# bar-graph-driver-16x9-ca-v2.net
KiCad netlist of a schematic drawn in EAGLE
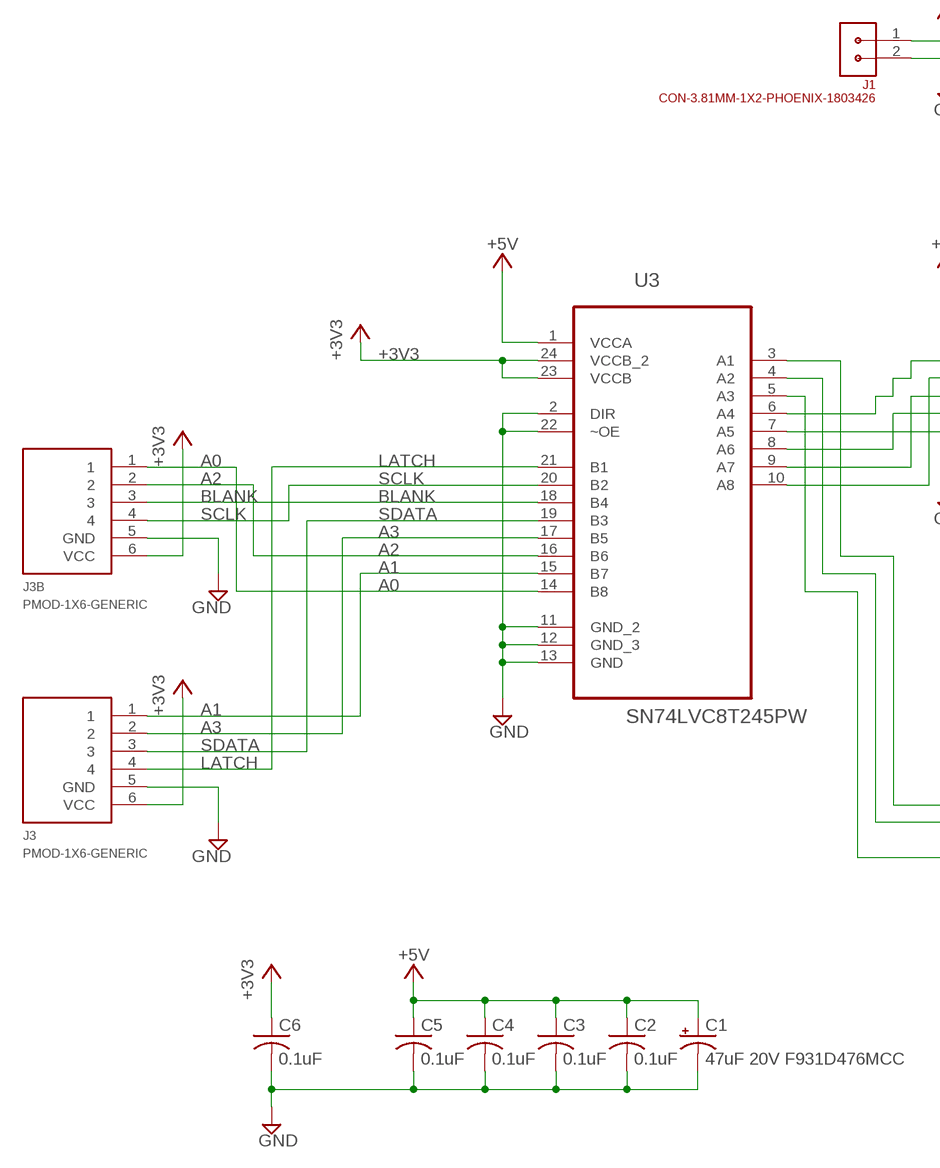
[diagram p0: schematic, sheet 1, part 1 of 2]
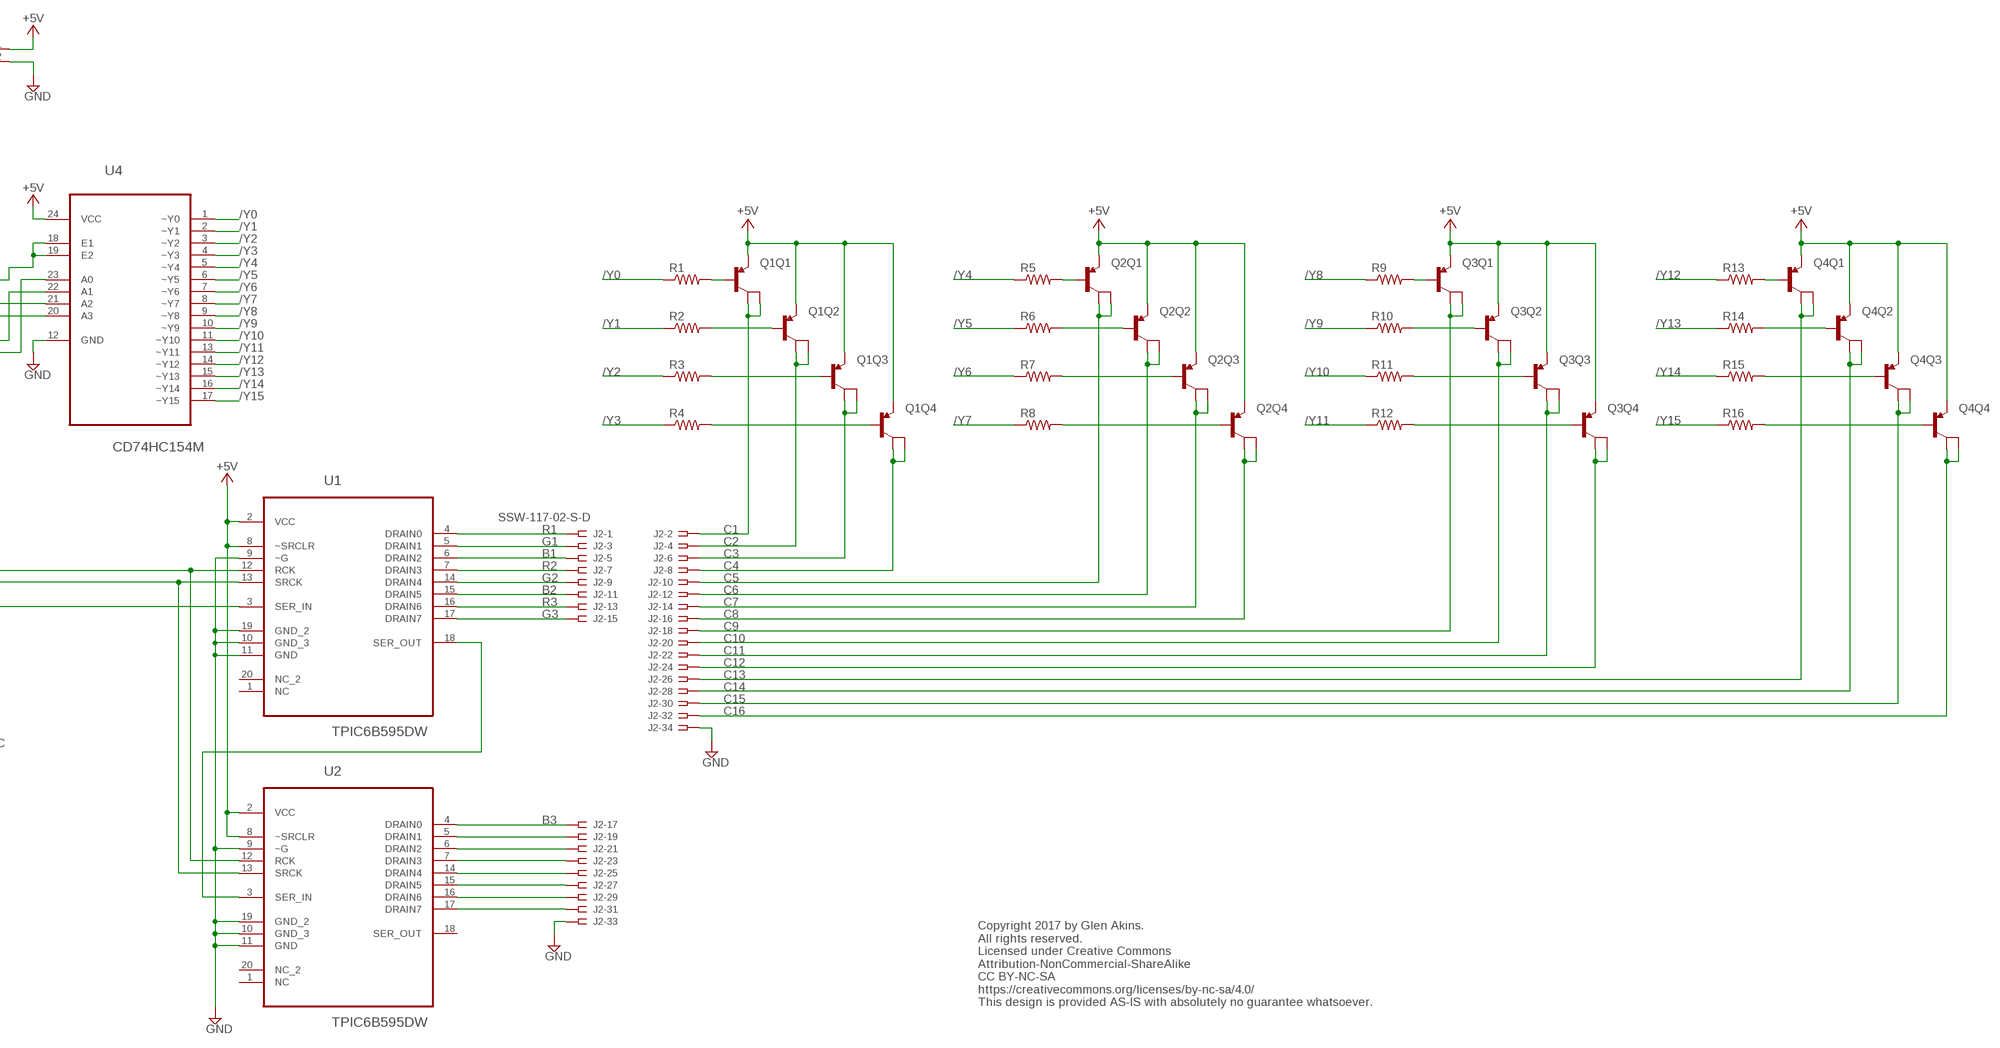
[diagram p1: schematic, sheet 1, part 2 of 2]

(export (version "E")
  (design (tool "Eeschema 10.0.6"))
  (components
    (comp (ref "C1")
      (value "47uF 20V F931D476MCC")
      (footprint "eagle-import:C_6032-28R")
      (libsource (lib "eagle-import") (part "CPOL-USC/6032-28R"))
    )
    (comp (ref "C2")
      (value "0.1uF")
      (footprint "eagle-import:C1206")
      (libsource (lib "eagle-import") (part "C-USC1206"))
    )
    (comp (ref "C3")
      (value "0.1uF")
      (footprint "eagle-import:C1206")
      (libsource (lib "eagle-import") (part "C-USC1206"))
    )
    (comp (ref "C4")
      (value "0.1uF")
      (footprint "eagle-import:C1206")
      (libsource (lib "eagle-import") (part "C-USC1206"))
    )
    (comp (ref "C5")
      (value "0.1uF")
      (footprint "eagle-import:C1206")
      (libsource (lib "eagle-import") (part "C-USC1206"))
    )
    (comp (ref "C6")
      (value "0.1uF")
      (footprint "eagle-import:C1206")
      (libsource (lib "eagle-import") (part "C-USC1206"))
    )
    (comp (ref "J1")
      (value "CON-3.81MM-1X2-PHOENIX-1803426")
      (footprint "eagle-import:CON-PHOENIX-1803426-3.81-1X2")
      (libsource (lib "eagle-import") (part "CON-3.81MM-1X2-PHOENIX-1803426"))
    )
    (comp (ref "J2")
      (value "SSW-117-02-S-D")
      (footprint "eagle-import:SSW-117-02-S-D")
      (libsource (lib "eagle-import") (part "SSW-117-02-S-D"))
    )
    (comp (ref "J3")
      (value "PMOD-1X6-GENERIC")
      (footprint "eagle-import:CON-PMOD-1X6")
      (libsource (lib "eagle-import") (part "PMOD-1X6-GENERIC"))
    )
    (comp (ref "J3B")
      (value "PMOD-1X6-GENERIC")
      (footprint "eagle-import:CON-PMOD-1X6")
      (libsource (lib "eagle-import") (part "PMOD-1X6-GENERIC"))
    )
    (comp (ref "Q1")
      (value "MMPQ2907A")
      (footprint "eagle-import:SO16")
      (libsource (lib "eagle-import") (part "MMPQ2907A"))
    )
    (comp (ref "Q2")
      (value "MMPQ2907A")
      (footprint "eagle-import:SO16")
      (libsource (lib "eagle-import") (part "MMPQ2907A"))
    )
    (comp (ref "Q3")
      (value "MMPQ2907A")
      (footprint "eagle-import:SO16")
      (libsource (lib "eagle-import") (part "MMPQ2907A"))
    )
    (comp (ref "Q4")
      (value "MMPQ2907A")
      (footprint "eagle-import:SO16")
      (libsource (lib "eagle-import") (part "MMPQ2907A"))
    )
    (comp (ref "R1")
      (value "R-US_R1206")
      (footprint "eagle-import:R1206")
      (libsource (lib "eagle-import") (part "R-US_R1206"))
    )
    (comp (ref "R2")
      (value "R-US_R1206")
      (footprint "eagle-import:R1206")
      (libsource (lib "eagle-import") (part "R-US_R1206"))
    )
    (comp (ref "R3")
      (value "R-US_R1206")
      (footprint "eagle-import:R1206")
      (libsource (lib "eagle-import") (part "R-US_R1206"))
    )
    (comp (ref "R4")
      (value "R-US_R1206")
      (footprint "eagle-import:R1206")
      (libsource (lib "eagle-import") (part "R-US_R1206"))
    )
    (comp (ref "R5")
      (value "R-US_R1206")
      (footprint "eagle-import:R1206")
      (libsource (lib "eagle-import") (part "R-US_R1206"))
    )
    (comp (ref "R6")
      (value "R-US_R1206")
      (footprint "eagle-import:R1206")
      (libsource (lib "eagle-import") (part "R-US_R1206"))
    )
    (comp (ref "R7")
      (value "R-US_R1206")
      (footprint "eagle-import:R1206")
      (libsource (lib "eagle-import") (part "R-US_R1206"))
    )
    (comp (ref "R8")
      (value "R-US_R1206")
      (footprint "eagle-import:R1206")
      (libsource (lib "eagle-import") (part "R-US_R1206"))
    )
    (comp (ref "R9")
      (value "R-US_R1206")
      (footprint "eagle-import:R1206")
      (libsource (lib "eagle-import") (part "R-US_R1206"))
    )
    (comp (ref "R10")
      (value "R-US_R1206")
      (footprint "eagle-import:R1206")
      (libsource (lib "eagle-import") (part "R-US_R1206"))
    )
    (comp (ref "R11")
      (value "R-US_R1206")
      (footprint "eagle-import:R1206")
      (libsource (lib "eagle-import") (part "R-US_R1206"))
    )
    (comp (ref "R12")
      (value "R-US_R1206")
      (footprint "eagle-import:R1206")
      (libsource (lib "eagle-import") (part "R-US_R1206"))
    )
    (comp (ref "R13")
      (value "R-US_R1206")
      (footprint "eagle-import:R1206")
      (libsource (lib "eagle-import") (part "R-US_R1206"))
    )
    (comp (ref "R14")
      (value "R-US_R1206")
      (footprint "eagle-import:R1206")
      (libsource (lib "eagle-import") (part "R-US_R1206"))
    )
    (comp (ref "R15")
      (value "R-US_R1206")
      (footprint "eagle-import:R1206")
      (libsource (lib "eagle-import") (part "R-US_R1206"))
    )
    (comp (ref "R16")
      (value "R-US_R1206")
      (footprint "eagle-import:R1206")
      (libsource (lib "eagle-import") (part "R-US_R1206"))
    )
    (comp (ref "U1")
      (value "TPIC6B595DW")
      (footprint "eagle-import:SOIC127P1030X265-20N")
      (libsource (lib "eagle-import") (part "TPIC6B595DW"))
    )
    (comp (ref "U2")
      (value "TPIC6B595DW")
      (footprint "eagle-import:SOIC127P1030X265-20N")
      (libsource (lib "eagle-import") (part "TPIC6B595DW"))
    )
    (comp (ref "U3")
      (value "SN74LVC8T245PW")
      (footprint "eagle-import:SOP65P640X120-24N")
      (fields (field (name "MPN") "SN74AVC8T245PW"))
      (libsource (lib "eagle-import") (part "SN74AVC8T245PW"))
    )
    (comp (ref "U4")
      (value "CD74HC154M")
      (footprint "eagle-import:SOIC127P1030X265-24N")
      (libsource (lib "eagle-import") (part "CD74HC154M"))
    )
  )
  (nets
    (net (code "1") (name "+3V3") (class "Default")
      (node (ref "C6") (pin "1") (pinfunction "1_1") (pintype "passive"))
      (node (ref "J3") (pin "6") (pinfunction "VCC_6") (pintype "bidirectional"))
      (node (ref "J3B") (pin "6") (pinfunction "VCC_6") (pintype "bidirectional"))
      (node (ref "U3") (pin "23") (pinfunction "VCCB_23") (pintype "power_in"))
      (node (ref "U3") (pin "24") (pinfunction "VCCB_2_24") (pintype "power_in"))
    )
    (net (code "2") (name "+5V") (class "Default")
      (node (ref "C1") (pin "+") (pinfunction "+_+") (pintype "passive"))
      (node (ref "C2") (pin "1") (pinfunction "1_1") (pintype "passive"))
      (node (ref "C3") (pin "1") (pinfunction "1_1") (pintype "passive"))
      (node (ref "C4") (pin "1") (pinfunction "1_1") (pintype "passive"))
      (node (ref "C5") (pin "1") (pinfunction "1_1") (pintype "passive"))
      (node (ref "J1") (pin "1") (pinfunction "1_1") (pintype "bidirectional"))
      (node (ref "Q1") (pin "10") (pinfunction "E_10") (pintype "passive"))
      (node (ref "Q1") (pin "12") (pinfunction "E_12") (pintype "passive"))
      (node (ref "Q1") (pin "14") (pinfunction "E_14") (pintype "passive"))
      (node (ref "Q1") (pin "16") (pinfunction "E_16") (pintype "passive"))
      (node (ref "Q2") (pin "10") (pinfunction "E_10") (pintype "passive"))
      (node (ref "Q2") (pin "12") (pinfunction "E_12") (pintype "passive"))
      (node (ref "Q2") (pin "14") (pinfunction "E_14") (pintype "passive"))
      (node (ref "Q2") (pin "16") (pinfunction "E_16") (pintype "passive"))
      (node (ref "Q3") (pin "10") (pinfunction "E_10") (pintype "passive"))
      (node (ref "Q3") (pin "12") (pinfunction "E_12") (pintype "passive"))
      (node (ref "Q3") (pin "14") (pinfunction "E_14") (pintype "passive"))
      (node (ref "Q3") (pin "16") (pinfunction "E_16") (pintype "passive"))
      (node (ref "Q4") (pin "10") (pinfunction "E_10") (pintype "passive"))
      (node (ref "Q4") (pin "12") (pinfunction "E_12") (pintype "passive"))
      (node (ref "Q4") (pin "14") (pinfunction "E_14") (pintype "passive"))
      (node (ref "Q4") (pin "16") (pinfunction "E_16") (pintype "passive"))
      (node (ref "U1") (pin "2") (pinfunction "VCC_2") (pintype "power_in"))
      (node (ref "U1") (pin "8") (pinfunction "~{SRCLR}_8") (pintype "input"))
      (node (ref "U2") (pin "2") (pinfunction "VCC_2") (pintype "power_in"))
      (node (ref "U2") (pin "8") (pinfunction "~{SRCLR}_8") (pintype "input"))
      (node (ref "U3") (pin "1") (pinfunction "VCCA_1") (pintype "power_in"))
      (node (ref "U4") (pin "24") (pinfunction "VCC_24") (pintype "power_in"))
    )
    (net (code "3") (name "/A0") (class "Default")
      (node (ref "J3B") (pin "1") (pinfunction "1_1") (pintype "bidirectional"))
      (node (ref "U3") (pin "14") (pinfunction "B8_14") (pintype "bidirectional"))
    )
    (net (code "4") (name "/A1") (class "Default")
      (node (ref "J3") (pin "1") (pinfunction "1_1") (pintype "bidirectional"))
      (node (ref "U3") (pin "15") (pinfunction "B7_15") (pintype "bidirectional"))
    )
    (net (code "5") (name "/A2") (class "Default")
      (node (ref "J3B") (pin "2") (pinfunction "2_2") (pintype "bidirectional"))
      (node (ref "U3") (pin "16") (pinfunction "B6_16") (pintype "bidirectional"))
    )
    (net (code "6") (name "/A3") (class "Default")
      (node (ref "J3") (pin "2") (pinfunction "2_2") (pintype "bidirectional"))
      (node (ref "U3") (pin "17") (pinfunction "B5_17") (pintype "bidirectional"))
    )
    (net (code "7") (name "/B1") (class "Default")
      (node (ref "J2") (pin "5") (pinfunction "1_5") (pintype "passive"))
      (node (ref "U1") (pin "6") (pinfunction "DRAIN2_6") (pintype "output"))
    )
    (net (code "8") (name "/B2") (class "Default")
      (node (ref "J2") (pin "11") (pinfunction "1_11") (pintype "passive"))
      (node (ref "U1") (pin "15") (pinfunction "DRAIN5_15") (pintype "output"))
    )
    (net (code "9") (name "/B3") (class "Default")
      (node (ref "J2") (pin "17") (pinfunction "1_17") (pintype "passive"))
      (node (ref "U2") (pin "4") (pinfunction "DRAIN0_4") (pintype "output"))
    )
    (net (code "10") (name "/BLANK") (class "Default")
      (node (ref "J3B") (pin "3") (pinfunction "3_3") (pintype "bidirectional"))
      (node (ref "U3") (pin "18") (pinfunction "B4_18") (pintype "bidirectional"))
    )
    (net (code "11") (name "/C1") (class "Default")
      (node (ref "J2") (pin "2") (pinfunction "1_2") (pintype "passive"))
      (node (ref "Q1") (pin "1") (pinfunction "C_1") (pintype "passive"))
      (node (ref "Q1") (pin "2") (pinfunction "C_2") (pintype "passive"))
    )
    (net (code "12") (name "/C2") (class "Default")
      (node (ref "J2") (pin "4") (pinfunction "1_4") (pintype "passive"))
      (node (ref "Q1") (pin "3") (pinfunction "C_3") (pintype "passive"))
      (node (ref "Q1") (pin "4") (pinfunction "C_4") (pintype "passive"))
    )
    (net (code "13") (name "/C3") (class "Default")
      (node (ref "J2") (pin "6") (pinfunction "1_6") (pintype "passive"))
      (node (ref "Q1") (pin "5") (pinfunction "C_5") (pintype "passive"))
      (node (ref "Q1") (pin "6") (pinfunction "C_6") (pintype "passive"))
    )
    (net (code "14") (name "/C4") (class "Default")
      (node (ref "J2") (pin "8") (pinfunction "1_8") (pintype "passive"))
      (node (ref "Q1") (pin "7") (pinfunction "C_7") (pintype "passive"))
      (node (ref "Q1") (pin "8") (pinfunction "C_8") (pintype "passive"))
    )
    (net (code "15") (name "/C5") (class "Default")
      (node (ref "J2") (pin "10") (pinfunction "1_10") (pintype "passive"))
      (node (ref "Q2") (pin "1") (pinfunction "C_1") (pintype "passive"))
      (node (ref "Q2") (pin "2") (pinfunction "C_2") (pintype "passive"))
    )
    (net (code "16") (name "/C6") (class "Default")
      (node (ref "J2") (pin "12") (pinfunction "1_12") (pintype "passive"))
      (node (ref "Q2") (pin "3") (pinfunction "C_3") (pintype "passive"))
      (node (ref "Q2") (pin "4") (pinfunction "C_4") (pintype "passive"))
    )
    (net (code "17") (name "/C7") (class "Default")
      (node (ref "J2") (pin "14") (pinfunction "1_14") (pintype "passive"))
      (node (ref "Q2") (pin "5") (pinfunction "C_5") (pintype "passive"))
      (node (ref "Q2") (pin "6") (pinfunction "C_6") (pintype "passive"))
    )
    (net (code "18") (name "/C8") (class "Default")
      (node (ref "J2") (pin "16") (pinfunction "1_16") (pintype "passive"))
      (node (ref "Q2") (pin "7") (pinfunction "C_7") (pintype "passive"))
      (node (ref "Q2") (pin "8") (pinfunction "C_8") (pintype "passive"))
    )
    (net (code "19") (name "/C9") (class "Default")
      (node (ref "J2") (pin "18") (pinfunction "1_18") (pintype "passive"))
      (node (ref "Q3") (pin "1") (pinfunction "C_1") (pintype "passive"))
      (node (ref "Q3") (pin "2") (pinfunction "C_2") (pintype "passive"))
    )
    (net (code "20") (name "/C10") (class "Default")
      (node (ref "J2") (pin "20") (pinfunction "1_20") (pintype "passive"))
      (node (ref "Q3") (pin "3") (pinfunction "C_3") (pintype "passive"))
      (node (ref "Q3") (pin "4") (pinfunction "C_4") (pintype "passive"))
    )
    (net (code "21") (name "/C11") (class "Default")
      (node (ref "J2") (pin "22") (pinfunction "1_22") (pintype "passive"))
      (node (ref "Q3") (pin "5") (pinfunction "C_5") (pintype "passive"))
      (node (ref "Q3") (pin "6") (pinfunction "C_6") (pintype "passive"))
    )
    (net (code "22") (name "/C12") (class "Default")
      (node (ref "J2") (pin "24") (pinfunction "1_24") (pintype "passive"))
      (node (ref "Q3") (pin "7") (pinfunction "C_7") (pintype "passive"))
      (node (ref "Q3") (pin "8") (pinfunction "C_8") (pintype "passive"))
    )
    (net (code "23") (name "/C13") (class "Default")
      (node (ref "J2") (pin "26") (pinfunction "1_26") (pintype "passive"))
      (node (ref "Q4") (pin "1") (pinfunction "C_1") (pintype "passive"))
      (node (ref "Q4") (pin "2") (pinfunction "C_2") (pintype "passive"))
    )
    (net (code "24") (name "/C14") (class "Default")
      (node (ref "J2") (pin "28") (pinfunction "1_28") (pintype "passive"))
      (node (ref "Q4") (pin "3") (pinfunction "C_3") (pintype "passive"))
      (node (ref "Q4") (pin "4") (pinfunction "C_4") (pintype "passive"))
    )
    (net (code "25") (name "/C15") (class "Default")
      (node (ref "J2") (pin "30") (pinfunction "1_30") (pintype "passive"))
      (node (ref "Q4") (pin "5") (pinfunction "C_5") (pintype "passive"))
      (node (ref "Q4") (pin "6") (pinfunction "C_6") (pintype "passive"))
    )
    (net (code "26") (name "/C16") (class "Default")
      (node (ref "J2") (pin "32") (pinfunction "1_32") (pintype "passive"))
      (node (ref "Q4") (pin "7") (pinfunction "C_7") (pintype "passive"))
      (node (ref "Q4") (pin "8") (pinfunction "C_8") (pintype "passive"))
    )
    (net (code "27") (name "/G1") (class "Default")
      (node (ref "J2") (pin "3") (pinfunction "1_3") (pintype "passive"))
      (node (ref "U1") (pin "5") (pinfunction "DRAIN1_5") (pintype "output"))
    )
    (net (code "28") (name "/G2") (class "Default")
      (node (ref "J2") (pin "9") (pinfunction "1_9") (pintype "passive"))
      (node (ref "U1") (pin "14") (pinfunction "DRAIN4_14") (pintype "output"))
    )
    (net (code "29") (name "/G3") (class "Default")
      (node (ref "J2") (pin "15") (pinfunction "1_15") (pintype "passive"))
      (node (ref "U1") (pin "17") (pinfunction "DRAIN7_17") (pintype "output"))
    )
    (net (code "30") (name "/LATCH") (class "Default")
      (node (ref "J3") (pin "4") (pinfunction "4_4") (pintype "bidirectional"))
      (node (ref "U3") (pin "21") (pinfunction "B1_21") (pintype "bidirectional"))
    )
    (net (code "31") (name "/R1") (class "Default")
      (node (ref "J2") (pin "1") (pinfunction "1_1") (pintype "passive"))
      (node (ref "U1") (pin "4") (pinfunction "DRAIN0_4") (pintype "output"))
    )
    (net (code "32") (name "/R2") (class "Default")
      (node (ref "J2") (pin "7") (pinfunction "1_7") (pintype "passive"))
      (node (ref "U1") (pin "7") (pinfunction "DRAIN3_7") (pintype "output"))
    )
    (net (code "33") (name "/R3") (class "Default")
      (node (ref "J2") (pin "13") (pinfunction "1_13") (pintype "passive"))
      (node (ref "U1") (pin "16") (pinfunction "DRAIN6_16") (pintype "output"))
    )
    (net (code "34") (name "/SCLK") (class "Default")
      (node (ref "J3B") (pin "4") (pinfunction "4_4") (pintype "bidirectional"))
      (node (ref "U3") (pin "20") (pinfunction "B2_20") (pintype "bidirectional"))
    )
    (net (code "35") (name "/SDATA") (class "Default")
      (node (ref "J3") (pin "3") (pinfunction "3_3") (pintype "bidirectional"))
      (node (ref "U3") (pin "19") (pinfunction "B3_19") (pintype "bidirectional"))
    )
    (net (code "36") (name "/{slash}Y0") (class "Default")
      (node (ref "R1") (pin "1") (pinfunction "1_1") (pintype "passive"))
      (node (ref "U4") (pin "1") (pinfunction "~{Y0}_1") (pintype "output"))
    )
    (net (code "37") (name "/{slash}Y1") (class "Default")
      (node (ref "R2") (pin "1") (pinfunction "1_1") (pintype "passive"))
      (node (ref "U4") (pin "2") (pinfunction "~{Y1}_2") (pintype "output"))
    )
    (net (code "38") (name "/{slash}Y2") (class "Default")
      (node (ref "R3") (pin "1") (pinfunction "1_1") (pintype "passive"))
      (node (ref "U4") (pin "3") (pinfunction "~{Y2}_3") (pintype "output"))
    )
    (net (code "39") (name "/{slash}Y3") (class "Default")
      (node (ref "R4") (pin "1") (pinfunction "1_1") (pintype "passive"))
      (node (ref "U4") (pin "4") (pinfunction "~{Y3}_4") (pintype "output"))
    )
    (net (code "40") (name "/{slash}Y4") (class "Default")
      (node (ref "R5") (pin "1") (pinfunction "1_1") (pintype "passive"))
      (node (ref "U4") (pin "5") (pinfunction "~{Y4}_5") (pintype "output"))
    )
    (net (code "41") (name "/{slash}Y5") (class "Default")
      (node (ref "R6") (pin "1") (pinfunction "1_1") (pintype "passive"))
      (node (ref "U4") (pin "6") (pinfunction "~{Y5}_6") (pintype "output"))
    )
    (net (code "42") (name "/{slash}Y6") (class "Default")
      (node (ref "R7") (pin "1") (pinfunction "1_1") (pintype "passive"))
      (node (ref "U4") (pin "7") (pinfunction "~{Y6}_7") (pintype "output"))
    )
    (net (code "43") (name "/{slash}Y7") (class "Default")
      (node (ref "R8") (pin "1") (pinfunction "1_1") (pintype "passive"))
      (node (ref "U4") (pin "8") (pinfunction "~{Y7}_8") (pintype "output"))
    )
    (net (code "44") (name "/{slash}Y8") (class "Default")
      (node (ref "R9") (pin "1") (pinfunction "1_1") (pintype "passive"))
      (node (ref "U4") (pin "9") (pinfunction "~{Y8}_9") (pintype "output"))
    )
    (net (code "45") (name "/{slash}Y9") (class "Default")
      (node (ref "R10") (pin "1") (pinfunction "1_1") (pintype "passive"))
      (node (ref "U4") (pin "10") (pinfunction "~{Y9}_10") (pintype "output"))
    )
    (net (code "46") (name "/{slash}Y10") (class "Default")
      (node (ref "R11") (pin "1") (pinfunction "1_1") (pintype "passive"))
      (node (ref "U4") (pin "11") (pinfunction "~{Y10}_11") (pintype "output"))
    )
    (net (code "47") (name "/{slash}Y11") (class "Default")
      (node (ref "R12") (pin "1") (pinfunction "1_1") (pintype "passive"))
      (node (ref "U4") (pin "13") (pinfunction "~{Y11}_13") (pintype "output"))
    )
    (net (code "48") (name "/{slash}Y12") (class "Default")
      (node (ref "R13") (pin "1") (pinfunction "1_1") (pintype "passive"))
      (node (ref "U4") (pin "14") (pinfunction "~{Y12}_14") (pintype "output"))
    )
    (net (code "49") (name "/{slash}Y13") (class "Default")
      (node (ref "R14") (pin "1") (pinfunction "1_1") (pintype "passive"))
      (node (ref "U4") (pin "15") (pinfunction "~{Y13}_15") (pintype "output"))
    )
    (net (code "50") (name "/{slash}Y14") (class "Default")
      (node (ref "R15") (pin "1") (pinfunction "1_1") (pintype "passive"))
      (node (ref "U4") (pin "16") (pinfunction "~{Y14}_16") (pintype "output"))
    )
    (net (code "51") (name "/{slash}Y15") (class "Default")
      (node (ref "R16") (pin "1") (pinfunction "1_1") (pintype "passive"))
      (node (ref "U4") (pin "17") (pinfunction "~{Y15}_17") (pintype "output"))
    )
    (net (code "52") (name "GND") (class "Default")
      (node (ref "C1") (pin "-") (pinfunction "-_-") (pintype "passive"))
      (node (ref "C2") (pin "2") (pinfunction "2_2") (pintype "passive"))
      (node (ref "C3") (pin "2") (pinfunction "2_2") (pintype "passive"))
      (node (ref "C4") (pin "2") (pinfunction "2_2") (pintype "passive"))
      (node (ref "C5") (pin "2") (pinfunction "2_2") (pintype "passive"))
      (node (ref "C6") (pin "2") (pinfunction "2_2") (pintype "passive"))
      (node (ref "J1") (pin "2") (pinfunction "2_2") (pintype "bidirectional"))
      (node (ref "J2") (pin "33") (pinfunction "1_33") (pintype "passive"))
      (node (ref "J2") (pin "34") (pinfunction "1_34") (pintype "passive"))
      (node (ref "J3") (pin "5") (pinfunction "GND_5") (pintype "power_in"))
      (node (ref "J3B") (pin "5") (pinfunction "GND_5") (pintype "power_in"))
      (node (ref "U1") (pin "10") (pinfunction "GND_3_10") (pintype "passive"))
      (node (ref "U1") (pin "11") (pinfunction "GND_11") (pintype "passive"))
      (node (ref "U1") (pin "19") (pinfunction "GND_2_19") (pintype "passive"))
      (node (ref "U1") (pin "9") (pinfunction "~{G}_9") (pintype "input"))
      (node (ref "U2") (pin "10") (pinfunction "GND_3_10") (pintype "passive"))
      (node (ref "U2") (pin "11") (pinfunction "GND_11") (pintype "passive"))
      (node (ref "U2") (pin "19") (pinfunction "GND_2_19") (pintype "passive"))
      (node (ref "U2") (pin "9") (pinfunction "~{G}_9") (pintype "input"))
      (node (ref "U3") (pin "11") (pinfunction "GND_2_11") (pintype "passive"))
      (node (ref "U3") (pin "12") (pinfunction "GND_3_12") (pintype "passive"))
      (node (ref "U3") (pin "13") (pinfunction "GND_13") (pintype "passive"))
      (node (ref "U3") (pin "2") (pinfunction "DIR_2") (pintype "input"))
      (node (ref "U3") (pin "22") (pinfunction "~{OE}_22") (pintype "input"))
      (node (ref "U4") (pin "12") (pinfunction "GND_12") (pintype "passive"))
    )
    (net (code "53") (name "Net-(J2K-1)") (class "Default")
      (node (ref "J2") (pin "19") (pinfunction "1_19") (pintype "passive"))
      (node (ref "U2") (pin "5") (pinfunction "DRAIN1_5") (pintype "output"))
    )
    (net (code "54") (name "Net-(J2N-1)") (class "Default")
      (node (ref "J2") (pin "21") (pinfunction "1_21") (pintype "passive"))
      (node (ref "U2") (pin "6") (pinfunction "DRAIN2_6") (pintype "output"))
    )
    (net (code "55") (name "Net-(J2P-1)") (class "Default")
      (node (ref "J2") (pin "23") (pinfunction "1_23") (pintype "passive"))
      (node (ref "U2") (pin "7") (pinfunction "DRAIN3_7") (pintype "output"))
    )
    (net (code "56") (name "Net-(J2R-1)") (class "Default")
      (node (ref "J2") (pin "25") (pinfunction "1_25") (pintype "passive"))
      (node (ref "U2") (pin "14") (pinfunction "DRAIN4_14") (pintype "output"))
    )
    (net (code "57") (name "Net-(J2T-1)") (class "Default")
      (node (ref "J2") (pin "27") (pinfunction "1_27") (pintype "passive"))
      (node (ref "U2") (pin "15") (pinfunction "DRAIN5_15") (pintype "output"))
    )
    (net (code "58") (name "Net-(J2V-1)") (class "Default")
      (node (ref "J2") (pin "29") (pinfunction "1_29") (pintype "passive"))
      (node (ref "U2") (pin "16") (pinfunction "DRAIN6_16") (pintype "output"))
    )
    (net (code "59") (name "Net-(J2Y-1)") (class "Default")
      (node (ref "J2") (pin "31") (pinfunction "1_31") (pintype "passive"))
      (node (ref "U2") (pin "17") (pinfunction "DRAIN7_17") (pintype "output"))
    )
    (net (code "60") (name "Net-(Q1A-B)") (class "Default")
      (node (ref "Q1") (pin "15") (pinfunction "B_15") (pintype "passive"))
      (node (ref "R1") (pin "2") (pinfunction "2_2") (pintype "passive"))
    )
    (net (code "61") (name "Net-(Q1B-B)") (class "Default")
      (node (ref "Q1") (pin "13") (pinfunction "B_13") (pintype "passive"))
      (node (ref "R2") (pin "2") (pinfunction "2_2") (pintype "passive"))
    )
    (net (code "62") (name "Net-(Q1C-B)") (class "Default")
      (node (ref "Q1") (pin "11") (pinfunction "B_11") (pintype "passive"))
      (node (ref "R3") (pin "2") (pinfunction "2_2") (pintype "passive"))
    )
    (net (code "63") (name "Net-(Q1D-B)") (class "Default")
      (node (ref "Q1") (pin "9") (pinfunction "B_9") (pintype "passive"))
      (node (ref "R4") (pin "2") (pinfunction "2_2") (pintype "passive"))
    )
    (net (code "64") (name "Net-(Q2A-B)") (class "Default")
      (node (ref "Q2") (pin "15") (pinfunction "B_15") (pintype "passive"))
      (node (ref "R5") (pin "2") (pinfunction "2_2") (pintype "passive"))
    )
    (net (code "65") (name "Net-(Q2B-B)") (class "Default")
      (node (ref "Q2") (pin "13") (pinfunction "B_13") (pintype "passive"))
      (node (ref "R6") (pin "2") (pinfunction "2_2") (pintype "passive"))
    )
    (net (code "66") (name "Net-(Q2C-B)") (class "Default")
      (node (ref "Q2") (pin "11") (pinfunction "B_11") (pintype "passive"))
      (node (ref "R7") (pin "2") (pinfunction "2_2") (pintype "passive"))
    )
    (net (code "67") (name "Net-(Q2D-B)") (class "Default")
      (node (ref "Q2") (pin "9") (pinfunction "B_9") (pintype "passive"))
      (node (ref "R8") (pin "2") (pinfunction "2_2") (pintype "passive"))
    )
    (net (code "68") (name "Net-(Q3A-B)") (class "Default")
      (node (ref "Q3") (pin "15") (pinfunction "B_15") (pintype "passive"))
      (node (ref "R9") (pin "2") (pinfunction "2_2") (pintype "passive"))
    )
    (net (code "69") (name "Net-(Q3B-B)") (class "Default")
      (node (ref "Q3") (pin "13") (pinfunction "B_13") (pintype "passive"))
      (node (ref "R10") (pin "2") (pinfunction "2_2") (pintype "passive"))
    )
    (net (code "70") (name "Net-(Q3C-B)") (class "Default")
      (node (ref "Q3") (pin "11") (pinfunction "B_11") (pintype "passive"))
      (node (ref "R11") (pin "2") (pinfunction "2_2") (pintype "passive"))
    )
    (net (code "71") (name "Net-(Q3D-B)") (class "Default")
      (node (ref "Q3") (pin "9") (pinfunction "B_9") (pintype "passive"))
      (node (ref "R12") (pin "2") (pinfunction "2_2") (pintype "passive"))
    )
    (net (code "72") (name "Net-(Q4A-B)") (class "Default")
      (node (ref "Q4") (pin "15") (pinfunction "B_15") (pintype "passive"))
      (node (ref "R13") (pin "2") (pinfunction "2_2") (pintype "passive"))
    )
    (net (code "73") (name "Net-(Q4B-B)") (class "Default")
      (node (ref "Q4") (pin "13") (pinfunction "B_13") (pintype "passive"))
      (node (ref "R14") (pin "2") (pinfunction "2_2") (pintype "passive"))
    )
    (net (code "74") (name "Net-(Q4C-B)") (class "Default")
      (node (ref "Q4") (pin "11") (pinfunction "B_11") (pintype "passive"))
      (node (ref "R15") (pin "2") (pinfunction "2_2") (pintype "passive"))
    )
    (net (code "75") (name "Net-(Q4D-B)") (class "Default")
      (node (ref "Q4") (pin "9") (pinfunction "B_9") (pintype "passive"))
      (node (ref "R16") (pin "2") (pinfunction "2_2") (pintype "passive"))
    )
    (net (code "76") (name "Net-(U1-RCK)") (class "Default")
      (node (ref "U1") (pin "12") (pinfunction "RCK_12") (pintype "input"))
      (node (ref "U2") (pin "12") (pinfunction "RCK_12") (pintype "input"))
      (node (ref "U3") (pin "3") (pinfunction "A1_3") (pintype "bidirectional"))
    )
    (net (code "77") (name "Net-(U1-SER_IN)") (class "Default")
      (node (ref "U1") (pin "3") (pinfunction "SER_IN_3") (pintype "input"))
      (node (ref "U3") (pin "5") (pinfunction "A3_5") (pintype "bidirectional"))
    )
    (net (code "78") (name "Net-(U1-SER_OUT)") (class "Default")
      (node (ref "U1") (pin "18") (pinfunction "SER_OUT_18") (pintype "output"))
      (node (ref "U2") (pin "3") (pinfunction "SER_IN_3") (pintype "input"))
    )
    (net (code "79") (name "Net-(U1-SRCK)") (class "Default")
      (node (ref "U1") (pin "13") (pinfunction "SRCK_13") (pintype "input"))
      (node (ref "U2") (pin "13") (pinfunction "SRCK_13") (pintype "input"))
      (node (ref "U3") (pin "4") (pinfunction "A2_4") (pintype "bidirectional"))
    )
    (net (code "80") (name "Net-(U3-A4)") (class "Default")
      (node (ref "U3") (pin "6") (pinfunction "A4_6") (pintype "bidirectional"))
      (node (ref "U4") (pin "18") (pinfunction "E1_18") (pintype "input"))
      (node (ref "U4") (pin "19") (pinfunction "E2_19") (pintype "input"))
    )
    (net (code "81") (name "Net-(U3-A5)") (class "Default")
      (node (ref "U3") (pin "7") (pinfunction "A5_7") (pintype "bidirectional"))
      (node (ref "U4") (pin "20") (pinfunction "A3_20") (pintype "input"))
    )
    (net (code "82") (name "Net-(U3-A6)") (class "Default")
      (node (ref "U3") (pin "8") (pinfunction "A6_8") (pintype "bidirectional"))
      (node (ref "U4") (pin "21") (pinfunction "A2_21") (pintype "input"))
    )
    (net (code "83") (name "Net-(U3-A7)") (class "Default")
      (node (ref "U3") (pin "9") (pinfunction "A7_9") (pintype "bidirectional"))
      (node (ref "U4") (pin "22") (pinfunction "A1_22") (pintype "input"))
    )
    (net (code "84") (name "Net-(U3-A8)") (class "Default")
      (node (ref "U3") (pin "10") (pinfunction "A8_10") (pintype "bidirectional"))
      (node (ref "U4") (pin "23") (pinfunction "A0_23") (pintype "input"))
    )
    (net (code "85") (name "unconnected-(U1-NC-Pad1)") (class "Default")
      (node (ref "U1") (pin "1") (pinfunction "NC_1") (pintype "no_connect"))
    )
    (net (code "86") (name "unconnected-(U1-NC_2-Pad20)") (class "Default")
      (node (ref "U1") (pin "20") (pinfunction "NC_2_20") (pintype "no_connect"))
    )
    (net (code "87") (name "unconnected-(U2-NC-Pad1)") (class "Default")
      (node (ref "U2") (pin "1") (pinfunction "NC_1") (pintype "no_connect"))
    )
    (net (code "88") (name "unconnected-(U2-NC_2-Pad20)") (class "Default")
      (node (ref "U2") (pin "20") (pinfunction "NC_2_20") (pintype "no_connect"))
    )
    (net (code "89") (name "unconnected-(U2-SER_OUT-Pad18)") (class "Default")
      (node (ref "U2") (pin "18") (pinfunction "SER_OUT_18") (pintype "output"))
    )
  )
)
